# blinkm_mk2a.net
KiCad netlist of a schematic drawn in EAGLE
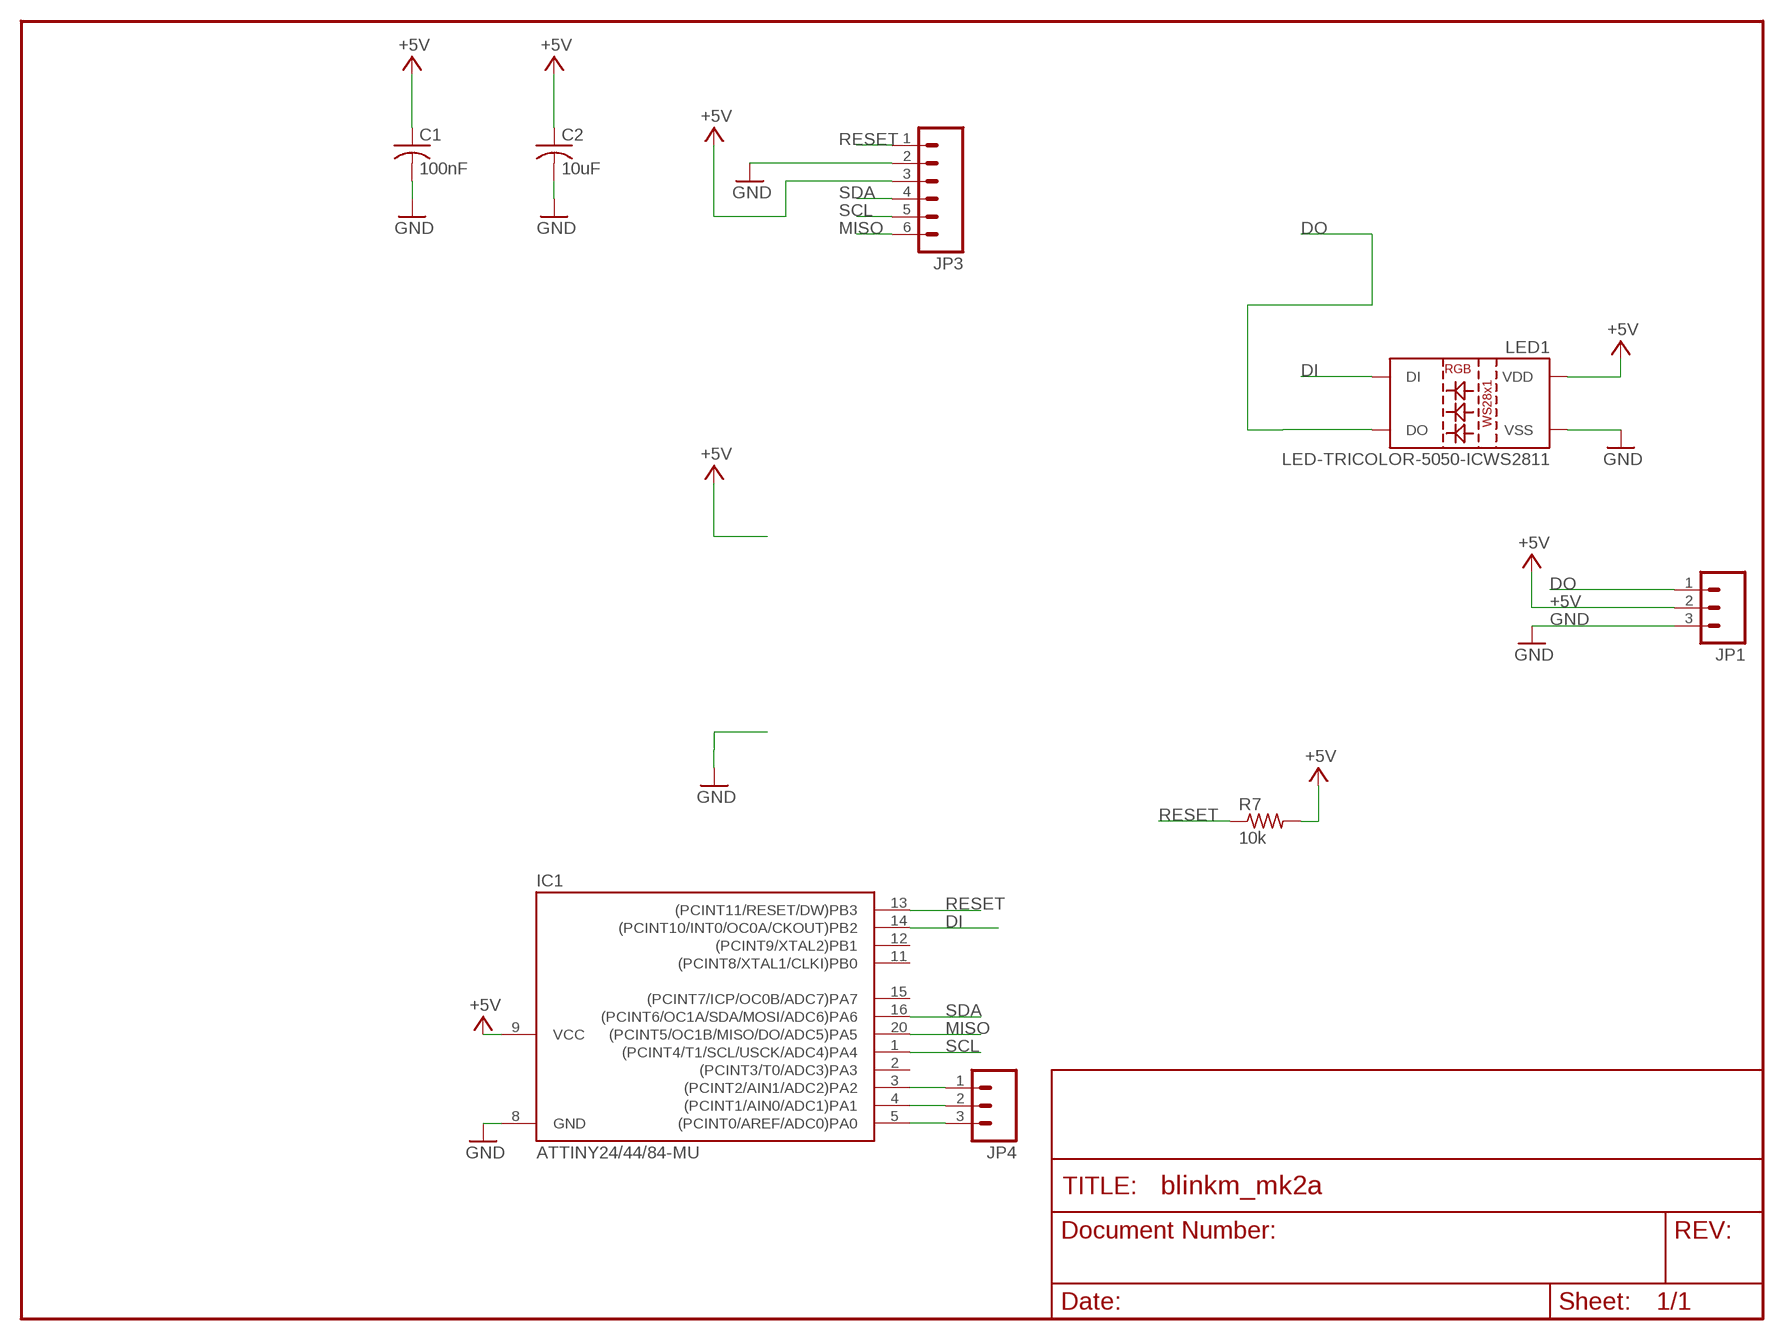
[diagram p0: schematic, sheet 1]

(export (version "E")
  (design (tool "Eeschema 10.0.6"))
  (components
    (comp (ref "C1")
      (value "100nF")
      (footprint "eagle-import:C0603")
      (libsource (lib "eagle-import") (part "C-USC0603"))
    )
    (comp (ref "C2")
      (value "10uF")
      (footprint "eagle-import:C0603")
      (libsource (lib "eagle-import") (part "C-USC0603"))
    )
    (comp (ref "IC1")
      (value "ATTINY24/44/84-MU")
      (footprint "eagle-import:QFN_MLF20")
      (libsource (lib "eagle-import") (part "ATTINY24/44/84-MU"))
    )
    (comp (ref "JP1")
      (value "M03PTH")
      (footprint "eagle-import:1X03")
      (libsource (lib "eagle-import") (part "M03PTH"))
    )
    (comp (ref "JP3")
      (value "M06SIP")
      (footprint "eagle-import:1X06")
      (libsource (lib "eagle-import") (part "M06SIP"))
    )
    (comp (ref "JP4")
      (value "M03PTH")
      (footprint "eagle-import:1X03")
      (libsource (lib "eagle-import") (part "M03PTH"))
    )
    (comp (ref "LED1")
      (value "LED-TRICOLOR-5050-ICWS2811")
      (footprint "eagle-import:LED-TRICOLOR-5050-IC")
      (libsource (lib "eagle-import") (part "LED-TRICOLOR-5050-ICWS2811"))
    )
    (comp (ref "R7")
      (value "10k")
      (footprint "eagle-import:R0603")
      (libsource (lib "eagle-import") (part "R-US_R0603"))
    )
  )
  (nets
    (net (code "1") (name "+5V") (class "Default")
      (node (ref "C1") (pin "1") (pinfunction "1_1") (pintype "passive"))
      (node (ref "C2") (pin "1") (pinfunction "1_1") (pintype "passive"))
      (node (ref "IC1") (pin "9") (pinfunction "VCC_9") (pintype "power_in"))
      (node (ref "JP1") (pin "2") (pinfunction "2_2") (pintype "passive"))
      (node (ref "JP3") (pin "3") (pinfunction "3_3") (pintype "passive"))
      (node (ref "LED1") (pin "3") (pinfunction "VDD_3") (pintype "bidirectional"))
      (node (ref "LED1") (pin "5") (pinfunction "VDD_5") (pintype "bidirectional"))
      (node (ref "R7") (pin "2") (pinfunction "2_2") (pintype "passive"))
    )
    (net (code "2") (name "/DI") (class "Default")
      (node (ref "IC1") (pin "14") (pinfunction "(PCINT10/INT0/OC0A/CKOUT)PB2_14") (pintype "bidirectional"))
      (node (ref "LED1") (pin "2") (pinfunction "DI_2") (pintype "bidirectional"))
    )
    (net (code "3") (name "/DO") (class "Default")
      (node (ref "JP1") (pin "1") (pinfunction "1_1") (pintype "passive"))
      (node (ref "LED1") (pin "1") (pinfunction "DO_1") (pintype "bidirectional"))
    )
    (net (code "4") (name "/MISO") (class "Default")
      (node (ref "IC1") (pin "20") (pinfunction "(PCINT5/OC1B/MISO/DO/ADC5)PA5_20") (pintype "bidirectional"))
      (node (ref "JP3") (pin "6") (pinfunction "6_6") (pintype "passive"))
    )
    (net (code "5") (name "/RESET") (class "Default")
      (node (ref "IC1") (pin "13") (pinfunction "(PCINT11/RESET/DW)PB3_13") (pintype "bidirectional"))
      (node (ref "JP3") (pin "1") (pinfunction "1_1") (pintype "passive"))
      (node (ref "R7") (pin "1") (pinfunction "1_1") (pintype "passive"))
    )
    (net (code "6") (name "/SCL") (class "Default")
      (node (ref "IC1") (pin "1") (pinfunction "(PCINT4/T1/SCL/USCK/ADC4)PA4_1") (pintype "bidirectional"))
      (node (ref "JP3") (pin "5") (pinfunction "5_5") (pintype "passive"))
    )
    (net (code "7") (name "/SDA") (class "Default")
      (node (ref "IC1") (pin "16") (pinfunction "(PCINT6/OC1A/SDA/MOSI/ADC6)PA6_16") (pintype "bidirectional"))
      (node (ref "JP3") (pin "4") (pinfunction "4_4") (pintype "passive"))
    )
    (net (code "8") (name "GND") (class "Default")
      (node (ref "C1") (pin "2") (pinfunction "2_2") (pintype "passive"))
      (node (ref "C2") (pin "2") (pinfunction "2_2") (pintype "passive"))
      (node (ref "IC1") (pin "8") (pinfunction "GND_8") (pintype "power_in"))
      (node (ref "JP1") (pin "3") (pinfunction "3_3") (pintype "passive"))
      (node (ref "JP3") (pin "2") (pinfunction "2_2") (pintype "passive"))
      (node (ref "LED1") (pin "6") (pinfunction "VSS_6") (pintype "bidirectional"))
    )
    (net (code "9") (name "Net-(IC1-(PCINT0{slash}AREF{slash}ADC0)PA0)") (class "Default")
      (node (ref "IC1") (pin "5") (pinfunction "(PCINT0/AREF/ADC0)PA0_5") (pintype "bidirectional"))
      (node (ref "JP4") (pin "3") (pinfunction "3_3") (pintype "passive"))
    )
    (net (code "10") (name "Net-(IC1-(PCINT1{slash}AIN0{slash}ADC1)PA1)") (class "Default")
      (node (ref "IC1") (pin "4") (pinfunction "(PCINT1/AIN0/ADC1)PA1_4") (pintype "bidirectional"))
      (node (ref "JP4") (pin "2") (pinfunction "2_2") (pintype "passive"))
    )
    (net (code "11") (name "Net-(IC1-(PCINT2{slash}AIN1{slash}ADC2)PA2)") (class "Default")
      (node (ref "IC1") (pin "3") (pinfunction "(PCINT2/AIN1/ADC2)PA2_3") (pintype "bidirectional"))
      (node (ref "JP4") (pin "1") (pinfunction "1_1") (pintype "passive"))
    )
    (net (code "12") (name "unconnected-(IC1-(PCINT3{slash}T0{slash}ADC3)PA3-Pad2)") (class "Default")
      (node (ref "IC1") (pin "2") (pinfunction "(PCINT3/T0/ADC3)PA3_2") (pintype "bidirectional"))
    )
    (net (code "13") (name "unconnected-(IC1-(PCINT7{slash}ICP{slash}OC0B{slash}ADC7)PA7-Pad15)") (class "Default")
      (node (ref "IC1") (pin "15") (pinfunction "(PCINT7/ICP/OC0B/ADC7)PA7_15") (pintype "bidirectional"))
    )
    (net (code "14") (name "unconnected-(IC1-(PCINT8{slash}XTAL1{slash}CLKI)PB0-Pad11)") (class "Default")
      (node (ref "IC1") (pin "11") (pinfunction "(PCINT8/XTAL1/CLKI)PB0_11") (pintype "bidirectional"))
    )
    (net (code "15") (name "unconnected-(IC1-(PCINT9{slash}XTAL2)PB1-Pad12)") (class "Default")
      (node (ref "IC1") (pin "12") (pinfunction "(PCINT9/XTAL2)PB1_12") (pintype "bidirectional"))
    )
  )
)
